# EPS_CTRL_AB_Supply.net
KiCad netlist of a schematic drawn in Altium Designer
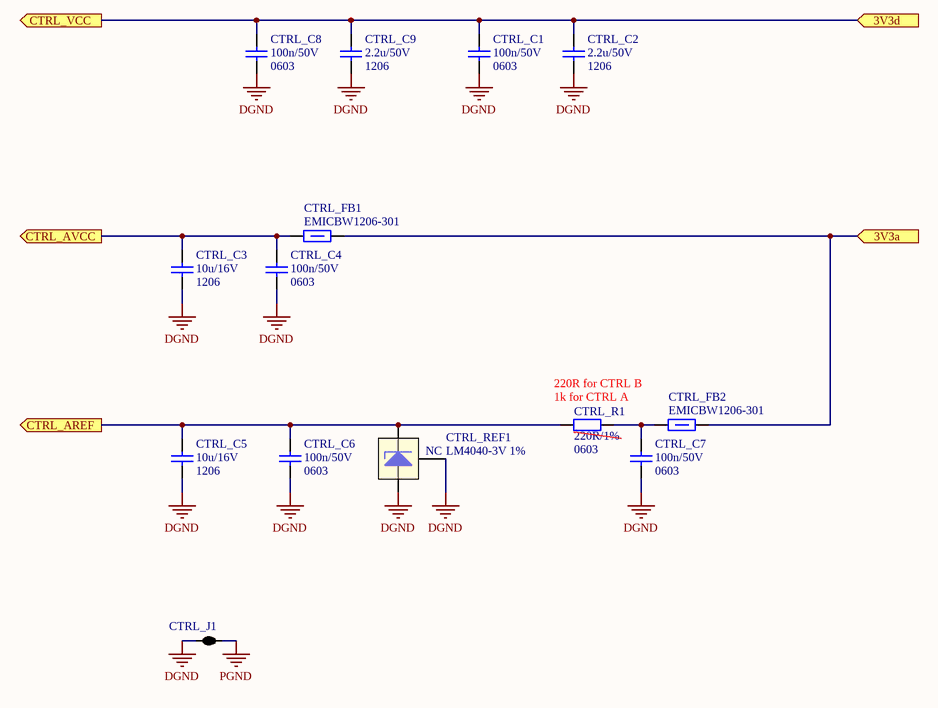
[diagram p0: EPS_CTRL_AB_Supply.SchDoc]

(export (version "E")
  (design (tool "Eeschema 10.0.6"))
  (components
    (comp (ref "CTRL_C1")
      (value "100n/50V")
      (footprint "SMD_Capacitor_0603")
      (description "Ceramic Cap Kemet COTS 100n/50V X7R 0603")
      (fields
        (field (name "MANUFACTURER") "Kemet")
        (field (name "MANUFACTURERPARTNUMBER") "C0603T104K5RALTU")
        (field (name "PACKAGE") "0603")
      )
      (libsource (lib "capacitors") (part "Cer_C0603T104K5RALTU"))
    )
    (comp (ref "CTRL_C2")
      (value "2.2u/50V")
      (footprint "SMD_Capacitor_1206")
      (description "Ceramic Cap Murata Automotive 2.2u/50V X7R 1206")
      (fields
        (field (name "MANUFACTURER") "Murata")
        (field (name "MANUFACTURERPARTNUMBER") "GCJ31CR71H225KA12L")
        (field (name "PACKAGE") "1206")
      )
      (libsource (lib "capacitors") (part "Cer_GCJ31CR71H225KA12L"))
    )
    (comp (ref "CTRL_C3")
      (value "10u/16V")
      (footprint "SMD_Capacitor_1206")
      (description "Ceramic Cap Kemet COTS 10u/16V X7R 1206")
      (fields
        (field (name "MANUFACTURERPARTNUMBER") "C1206T106K4RACTU")
        (field (name "MANUFACTURER") "Kemet")
        (field (name "PACKGE") "1206")
      )
      (libsource (lib "capacitors") (part "Cer_C1206T106K4RACTU"))
    )
    (comp (ref "CTRL_C4")
      (value "100n/50V")
      (footprint "SMD_Capacitor_0603")
      (description "Ceramic Cap Kemet COTS 100n/50V X7R 0603")
      (fields
        (field (name "MANUFACTURER") "Kemet")
        (field (name "MANUFACTURERPARTNUMBER") "C0603T104K5RALTU")
        (field (name "PACKAGE") "0603")
      )
      (libsource (lib "capacitors") (part "Cer_C0603T104K5RALTU"))
    )
    (comp (ref "CTRL_C5")
      (value "10u/16V")
      (footprint "SMD_Capacitor_1206")
      (description "Ceramic Cap Kemet COTS 10u/16V X7R 1206")
      (fields
        (field (name "MANUFACTURERPARTNUMBER") "C1206T106K4RACTU")
        (field (name "MANUFACTURER") "Kemet")
        (field (name "PACKGE") "1206")
      )
      (libsource (lib "capacitors") (part "Cer_C1206T106K4RACTU"))
    )
    (comp (ref "CTRL_C6")
      (value "100n/50V")
      (footprint "SMD_Capacitor_0603")
      (description "Ceramic Cap Kemet COTS 100n/50V X7R 0603")
      (fields
        (field (name "MANUFACTURER") "Kemet")
        (field (name "MANUFACTURERPARTNUMBER") "C0603T104K5RALTU")
        (field (name "PACKAGE") "0603")
      )
      (libsource (lib "capacitors") (part "Cer_C0603T104K5RALTU"))
    )
    (comp (ref "CTRL_C7")
      (value "100n/50V")
      (footprint "SMD_Capacitor_0603")
      (description "Ceramic Cap Kemet COTS 100n/50V X7R 0603")
      (fields
        (field (name "MANUFACTURER") "Kemet")
        (field (name "MANUFACTURERPARTNUMBER") "C0603T104K5RALTU")
        (field (name "PACKAGE") "0603")
      )
      (libsource (lib "capacitors") (part "Cer_C0603T104K5RALTU"))
    )
    (comp (ref "CTRL_C8")
      (value "100n/50V")
      (footprint "SMD_Capacitor_0603")
      (description "Ceramic Cap Kemet COTS 100n/50V X7R 0603")
      (fields
        (field (name "MANUFACTURER") "Kemet")
        (field (name "MANUFACTURERPARTNUMBER") "C0603T104K5RALTU")
        (field (name "PACKAGE") "0603")
      )
      (libsource (lib "capacitors") (part "Cer_C0603T104K5RALTU"))
    )
    (comp (ref "CTRL_C9")
      (value "2.2u/50V")
      (footprint "SMD_Capacitor_1206")
      (description "Ceramic Cap Murata Automotive 2.2u/50V X7R 1206")
      (fields
        (field (name "MANUFACTURER") "Murata")
        (field (name "MANUFACTURERPARTNUMBER") "GCJ31CR71H225KA12L")
        (field (name "PACKAGE") "1206")
      )
      (libsource (lib "capacitors") (part "Cer_GCJ31CR71H225KA12L"))
    )
    (comp (ref "CTRL_FB1")
      (value "*")
      (footprint "1206")
      (description "Ferrite Bead")
      (fields (field (name "MANUFACTURER") "Fengua") (field (name "MANUFACTURERPARTNUMBER") "EMICBW1206-301"))
      (libsource (lib "inductors") (part "FerriteBead"))
    )
    (comp (ref "CTRL_FB2")
      (value "*")
      (footprint "1206")
      (description "Ferrite Bead")
      (fields (field (name "MANUFACTURER") "Fengua") (field (name "MANUFACTURERPARTNUMBER") "EMICBW1206-301"))
      (libsource (lib "inductors") (part "FerriteBead"))
    )
    (comp (ref "CTRL_J1")
      (value "2 way net tie junction")
      (footprint "2way_LP")
      (libsource (lib "NetTieLib") (part "2way"))
    )
    (comp (ref "CTRL_R1")
      (value "220R/1%")
      (footprint "SMD_Resistor_0603")
      (fields (field (name "PACKAGE") "0603"))
      (libsource (lib "resistors") (part "Res"))
    )
    (comp (ref "CTRL_REF1")
      (value "LM4040-3V 1%")
      (footprint "SOT23-3")
      (description "Shunt V-REF, 3V, 1%, SOT23-3")
      (fields
        (field (name "MANUFACTURERPARTNUMBER") "LM4040DIM3-3.0")
        (field (name "MANUFACTURER") "Texas Instruments")
      )
      (libsource (lib "diodes") (part "LM4040DIM3-3.0"))
    )
  )
  (nets
    (net (code "1") (name "/3V3a") (class "Default")
      (node (ref "CTRL_FB1") (pin "1") (pinfunction "1_1") (pintype "passive"))
      (node (ref "CTRL_FB2") (pin "1") (pinfunction "1_1") (pintype "passive"))
    )
    (net (code "2") (name "/3V3d") (class "Default")
      (node (ref "CTRL_C1") (pin "1") (pinfunction "1_1") (pintype "passive"))
      (node (ref "CTRL_C2") (pin "1") (pinfunction "1_1") (pintype "passive"))
      (node (ref "CTRL_C8") (pin "1") (pinfunction "1_1") (pintype "passive"))
      (node (ref "CTRL_C9") (pin "1") (pinfunction "1_1") (pintype "passive"))
    )
    (net (code "3") (name "/CTRL_AREF") (class "Default")
      (node (ref "CTRL_C5") (pin "1") (pinfunction "1_1") (pintype "passive"))
      (node (ref "CTRL_C6") (pin "1") (pinfunction "1_1") (pintype "passive"))
      (node (ref "CTRL_R1") (pin "1") (pinfunction "1_1") (pintype "passive"))
      (node (ref "CTRL_REF1") (pin "1") (pinfunction "K_1") (pintype "passive"))
    )
    (net (code "4") (name "/CTRL_AVCC") (class "Default")
      (node (ref "CTRL_C3") (pin "1") (pinfunction "1_1") (pintype "passive"))
      (node (ref "CTRL_C4") (pin "1") (pinfunction "1_1") (pintype "passive"))
      (node (ref "CTRL_FB1") (pin "2") (pinfunction "2_2") (pintype "passive"))
    )
    (net (code "5") (name "DGND") (class "Default")
      (node (ref "CTRL_C1") (pin "2") (pinfunction "2_2") (pintype "passive"))
      (node (ref "CTRL_C2") (pin "2") (pinfunction "2_2") (pintype "passive"))
      (node (ref "CTRL_C3") (pin "2") (pinfunction "2_2") (pintype "passive"))
      (node (ref "CTRL_C4") (pin "2") (pinfunction "2_2") (pintype "passive"))
      (node (ref "CTRL_C5") (pin "2") (pinfunction "2_2") (pintype "passive"))
      (node (ref "CTRL_C6") (pin "2") (pinfunction "2_2") (pintype "passive"))
      (node (ref "CTRL_C7") (pin "2") (pinfunction "2_2") (pintype "passive"))
      (node (ref "CTRL_C8") (pin "2") (pinfunction "2_2") (pintype "passive"))
      (node (ref "CTRL_C9") (pin "2") (pinfunction "2_2") (pintype "passive"))
      (node (ref "CTRL_J1") (pin "2") (pinfunction "2_2") (pintype "passive"))
      (node (ref "CTRL_REF1") (pin "2") (pinfunction "A_2") (pintype "passive"))
      (node (ref "CTRL_REF1") (pin "3") (pinfunction "NC_3") (pintype "passive"))
    )
    (net (code "6") (name "Net-(CTRL_C7-Pad1)") (class "Default")
      (node (ref "CTRL_C7") (pin "1") (pinfunction "1_1") (pintype "passive"))
      (node (ref "CTRL_FB2") (pin "2") (pinfunction "2_2") (pintype "passive"))
      (node (ref "CTRL_R1") (pin "2") (pinfunction "2_2") (pintype "passive"))
    )
    (net (code "7") (name "PGND") (class "Default")
      (node (ref "CTRL_J1") (pin "1") (pinfunction "1_1") (pintype "passive"))
    )
  )
)
